# RTCE.net
KiCad netlist of a schematic drawn in Altium Designer
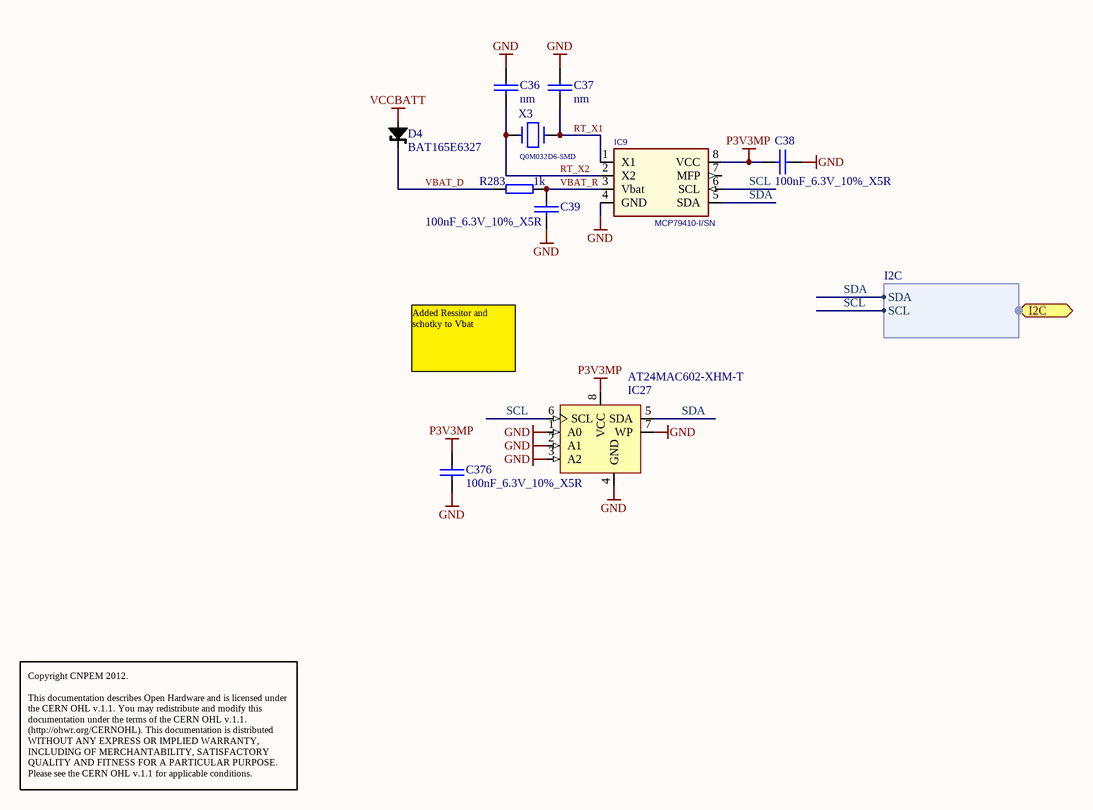
[diagram p0: RTCE.SchDoc]

(export (version "E")
  (design (tool "Eeschema 10.0.6"))
  (components
    (comp (ref "C36")
      (value "nm")
      (footprint "0402C")
      (description "Capacitor SMD")
      (libsource (lib "LIBRARY_SCH") (part "CAP_SMD_0201"))
    )
    (comp (ref "C37")
      (value "nm")
      (footprint "0402C")
      (description "Capacitor SMD")
      (libsource (lib "LIBRARY_SCH") (part "CAP_SMD_0201"))
    )
    (comp (ref "C38")
      (value "100nF_6.3V_10%_X5R")
      (footprint "0201C")
      (description "Capacitor SMD")
      (libsource (lib "LIBRARY_SCH") (part "CAP_SMD_0201"))
    )
    (comp (ref "C39")
      (value "100nF_6.3V_10%_X5R")
      (footprint "0201C")
      (description "Capacitor SMD")
      (libsource (lib "LIBRARY_SCH") (part "CAP_SMD_0201"))
    )
    (comp (ref "C376")
      (value "100nF_6.3V_10%_X5R")
      (footprint "0201C")
      (description "Capacitor SMD")
      (libsource (lib "LIBRARY_SCH") (part "CAP_SMD_0201"))
    )
    (comp (ref "D4")
      (value "BAT165E6327")
      (footprint "SOD323")
      (description "500mA, 40V, Shottky Diode")
      (libsource (lib "LIBRARY_SCH") (part "D_BAT165"))
    )
    (comp (ref "IC9")
      (value "MCP79410-I/SN")
      (footprint "SO-8")
      (description "RTC with 1k EEPROM and RAM")
      (libsource (lib "LIBRARY_SCH") (part "RTC_MCP79410"))
    )
    (comp (ref "IC27")
      (value "AT24MAC602-XHM-T")
      (footprint "TSSOP-8")
      (description "Serial 2K EEPROM+ 48bit MAC")
      (libsource (lib "LIBRARY_SCH") (part "MEM_24MAC602"))
    )
    (comp (ref "R283")
      (value "1k")
      (footprint "0402R")
      (description "SMD Resistor")
      (libsource (lib "LIBRARY_SCH") (part "RES_0402"))
    )
    (comp (ref "X3")
      (value "Q0M032D6-SMD")
      (footprint "crystal_85SMX")
      (description "Crystal oscillator 32k (Maritex)")
      (libsource (lib "LIBRARY_SCH") (part "X_CRYSTAL_32k_SMD"))
    )
  )
  (nets
    (net (code "2") (name "/RT_X1") (class "Default")
      (node (ref "C37") (pin "2") (pinfunction "2_2") (pintype "passive"))
      (node (ref "IC9") (pin "1") (pinfunction "X1_1") (pintype "passive"))
      (node (ref "X3") (pin "1") (pinfunction "1_1") (pintype "passive"))
    )
    (net (code "3") (name "/RT_X2") (class "Default")
      (node (ref "C36") (pin "2") (pinfunction "2_2") (pintype "passive"))
      (node (ref "IC9") (pin "2") (pinfunction "X2_2") (pintype "passive"))
      (node (ref "X3") (pin "4") (pinfunction "4_4") (pintype "passive"))
    )
    (net (code "4") (name "/SCL") (class "Default")
      (node (ref "IC27") (pin "6") (pinfunction "SCL_6") (pintype "input"))
      (node (ref "IC9") (pin "6") (pinfunction "SCL_6") (pintype "input"))
    )
    (net (code "5") (name "/SDA") (class "Default")
      (node (ref "IC27") (pin "5") (pinfunction "SDA_5") (pintype "bidirectional"))
      (node (ref "IC9") (pin "5") (pinfunction "SDA_5") (pintype "bidirectional"))
    )
    (net (code "6") (name "/VBAT_D") (class "Default")
      (node (ref "D4") (pin "K") (pinfunction "K_K") (pintype "passive"))
      (node (ref "R283") (pin "1") (pinfunction "1_1") (pintype "passive"))
    )
    (net (code "7") (name "/VBAT_R") (class "Default")
      (node (ref "C39") (pin "1") (pinfunction "1_1") (pintype "passive"))
      (node (ref "IC9") (pin "3") (pinfunction "Vbat_3") (pintype "power_in"))
      (node (ref "R283") (pin "2") (pinfunction "2_2") (pintype "passive"))
    )
    (net (code "9") (name "GND") (class "Default")
      (node (ref "C36") (pin "1") (pinfunction "1_1") (pintype "passive"))
      (node (ref "C37") (pin "1") (pinfunction "1_1") (pintype "passive"))
      (node (ref "C376") (pin "2") (pinfunction "2_2") (pintype "passive"))
      (node (ref "C38") (pin "2") (pinfunction "2_2") (pintype "passive"))
      (node (ref "C39") (pin "2") (pinfunction "2_2") (pintype "passive"))
      (node (ref "IC27") (pin "1") (pinfunction "A0_1") (pintype "input"))
      (node (ref "IC27") (pin "2") (pinfunction "A1_2") (pintype "input"))
      (node (ref "IC27") (pin "3") (pinfunction "A2_3") (pintype "input"))
      (node (ref "IC27") (pin "4") (pinfunction "GND_4") (pintype "power_in"))
      (node (ref "IC27") (pin "7") (pinfunction "WP_7") (pintype "passive"))
      (node (ref "IC9") (pin "4") (pinfunction "GND_4") (pintype "power_in"))
    )
    (net (code "10") (name "P3V3MP") (class "Default")
      (node (ref "C376") (pin "1") (pinfunction "1_1") (pintype "passive"))
      (node (ref "C38") (pin "1") (pinfunction "1_1") (pintype "passive"))
      (node (ref "IC27") (pin "8") (pinfunction "VCC_8") (pintype "power_in"))
      (node (ref "IC9") (pin "8") (pinfunction "VCC_8") (pintype "power_in"))
    )
    (net (code "11") (name "VCCBATT") (class "Default")
      (node (ref "D4") (pin "A") (pinfunction "A_A") (pintype "passive"))
    )
    (net (code "12") (name "unconnected-(IC9-MFP-Pad7)") (class "Default")
      (node (ref "IC9") (pin "7") (pinfunction "MFP_7") (pintype "output"))
    )
  )
)
